# Sheet1.net
KiCad netlist of a schematic drawn in Altium Designer
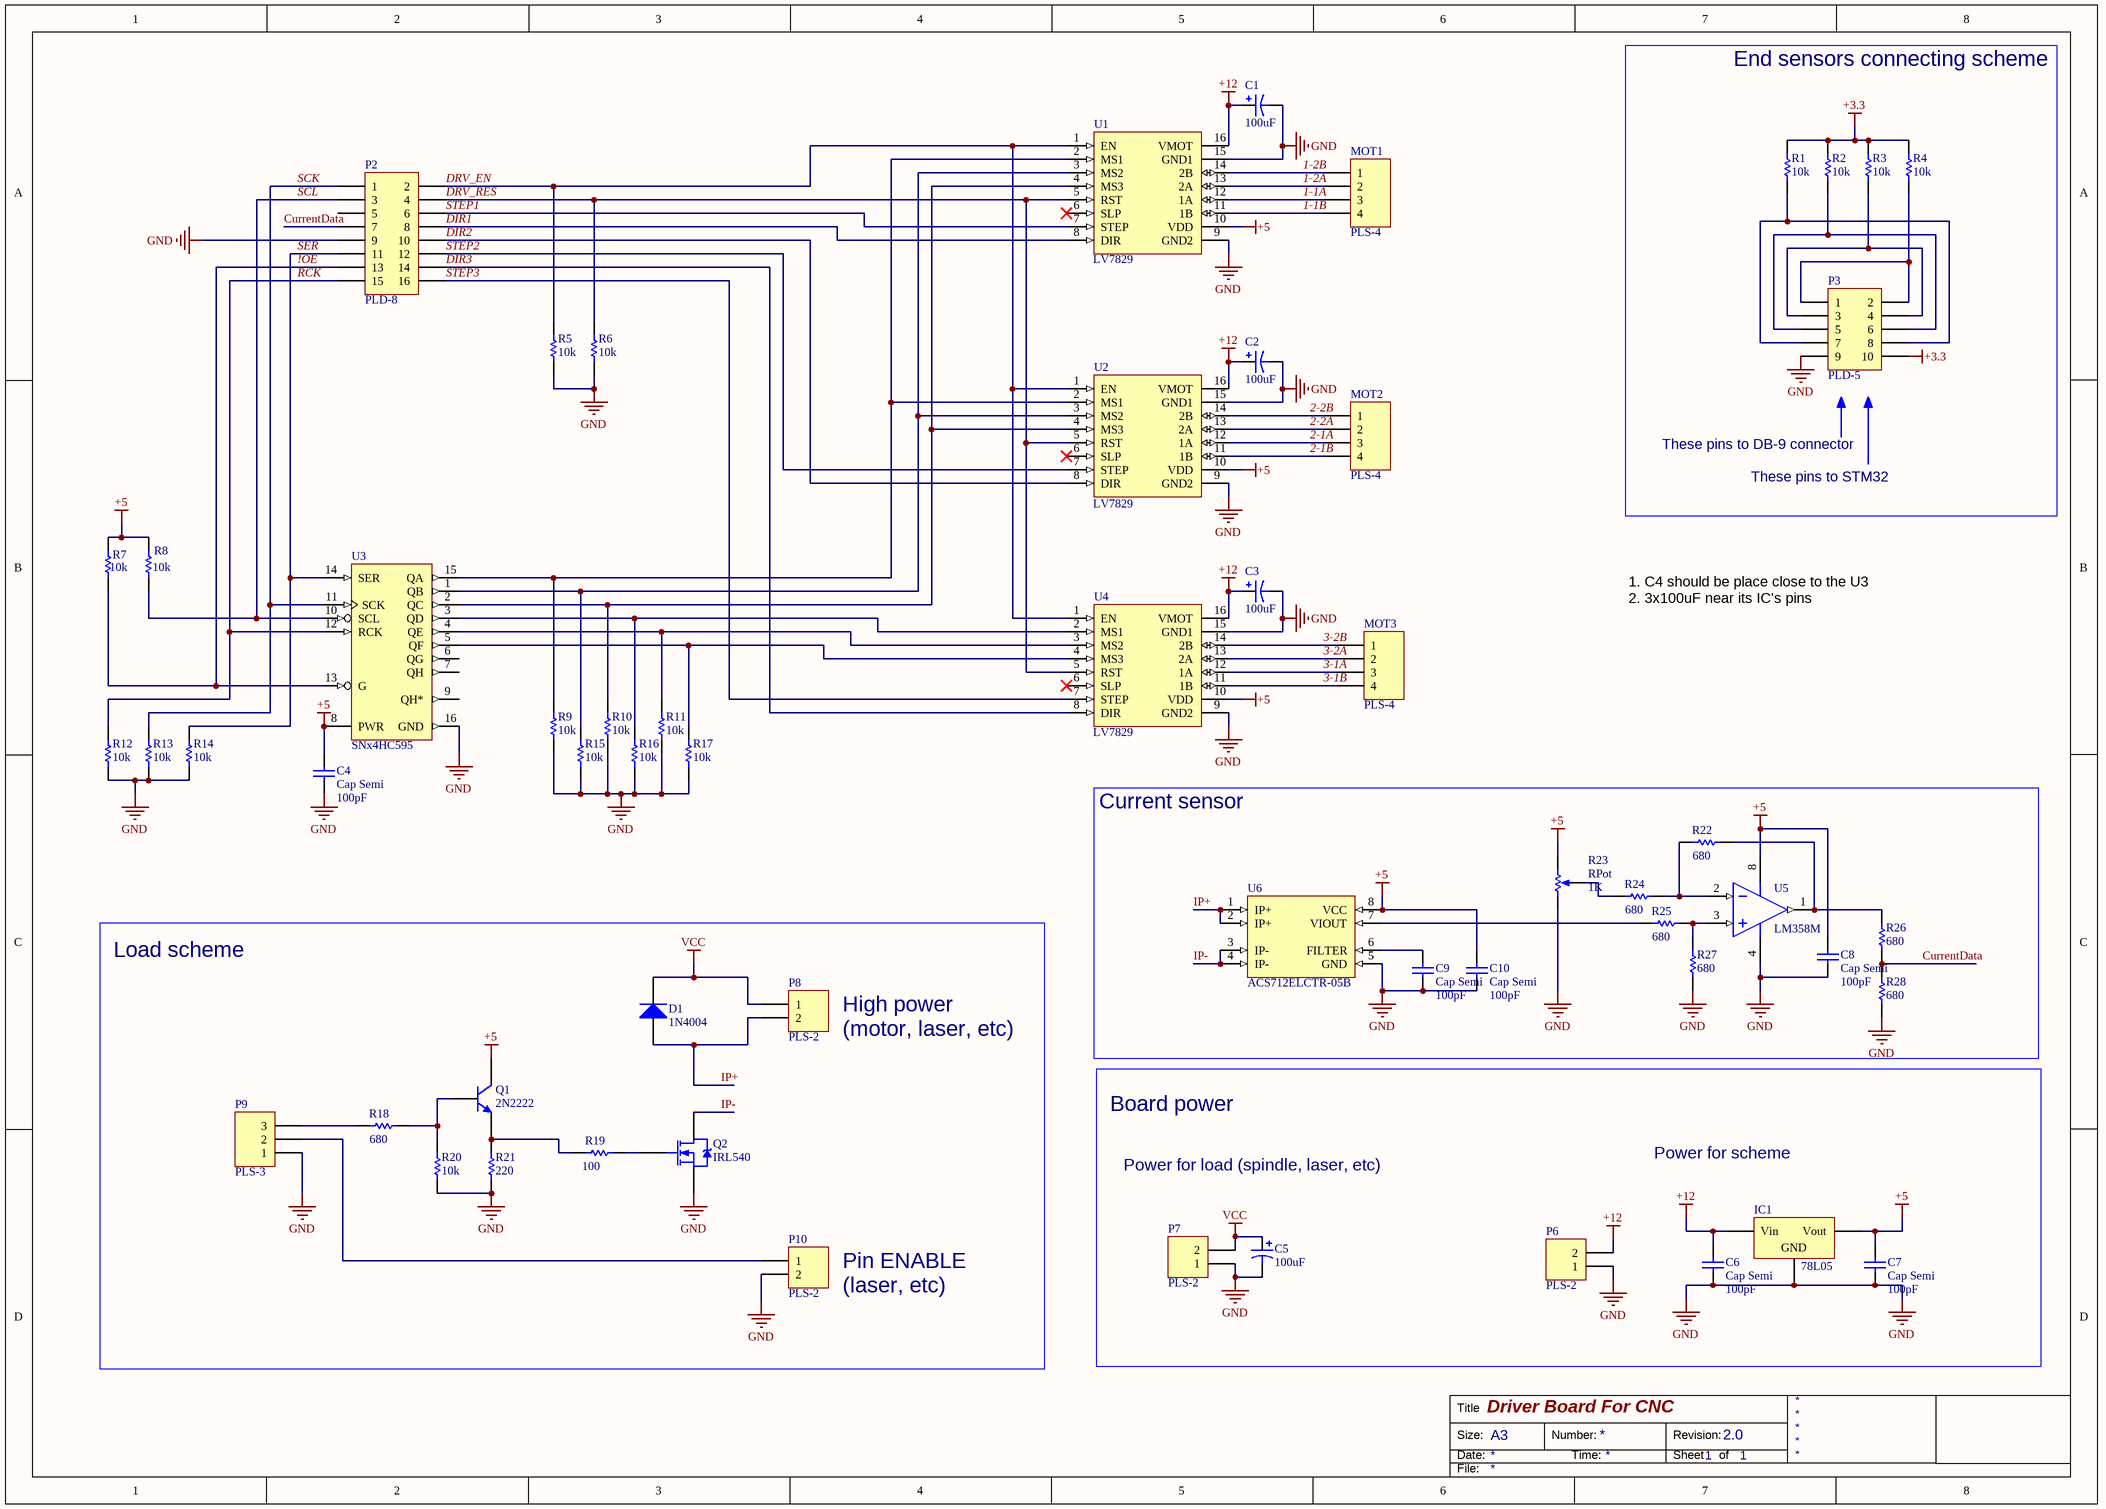
[diagram p0: Sheet1.SchDoc]

(export (version "E")
  (design (tool "Eeschema 10.0.6"))
  (components
    (comp (ref "C1")
      (value "100uF")
      (footprint "UD-6,3X5,8_NICHICON")
      (description "Polarized Capacitor (Radial)")
      (fields (field (name "Comment") "Cap Pol1") (field (name "PUBLISHER") "Altium Limited"))
      (libsource (lib "DriverBoardForCNC") (part "Cap Pol1"))
    )
    (comp (ref "C2")
      (value "100uF")
      (footprint "UD-6,3X5,8_NICHICON")
      (description "Polarized Capacitor (Radial)")
      (fields (field (name "Comment") "Cap Pol1") (field (name "PUBLISHER") "Altium Limited"))
      (libsource (lib "DriverBoardForCNC") (part "Cap Pol1"))
    )
    (comp (ref "C3")
      (value "100uF")
      (footprint "UD-6,3X5,8_NICHICON")
      (description "Polarized Capacitor (Radial)")
      (fields (field (name "Comment") "Cap Pol1") (field (name "PUBLISHER") "Altium Limited"))
      (libsource (lib "DriverBoardForCNC") (part "Cap Pol1"))
    )
    (comp (ref "C4")
      (value "Cap Semi")
      (footprint "C1206")
      (description "Capacitor (Semiconductor SIM Model)")
      (fields (field (name "ALTIUM_VALUE") "100pF") (field (name "PUBLISHER") "Altium Limited"))
      (libsource (lib "USB-RS485-unit") (part "Cap Semi"))
    )
    (comp (ref "C5")
      (value "100uF")
      (footprint "UD-6,3X5,8_NICHICON")
      (description "Polarized Capacitor (Radial)")
      (fields (field (name "Comment") "Cap Pol1") (field (name "PUBLISHER") "Altium Limited"))
      (libsource (lib "DriverBoardForCNC") (part "Cap Pol1"))
    )
    (comp (ref "C6")
      (value "Cap Semi")
      (footprint "C1206")
      (description "Capacitor (Semiconductor SIM Model)")
      (fields (field (name "ALTIUM_VALUE") "100pF") (field (name "PUBLISHER") "Altium Limited"))
      (libsource (lib "USB-RS485-unit") (part "Cap Semi"))
    )
    (comp (ref "C7")
      (value "Cap Semi")
      (footprint "C1206")
      (description "Capacitor (Semiconductor SIM Model)")
      (fields (field (name "ALTIUM_VALUE") "100pF") (field (name "PUBLISHER") "Altium Limited"))
      (libsource (lib "USB-RS485-unit") (part "Cap Semi"))
    )
    (comp (ref "C8")
      (value "Cap Semi")
      (footprint "C1206")
      (description "Capacitor (Semiconductor SIM Model)")
      (fields (field (name "ALTIUM_VALUE") "100pF") (field (name "PUBLISHER") "Altium Limited"))
      (libsource (lib "USB-RS485-unit") (part "Cap Semi"))
    )
    (comp (ref "C9")
      (value "Cap Semi")
      (footprint "C1206")
      (description "Capacitor (Semiconductor SIM Model)")
      (fields (field (name "ALTIUM_VALUE") "100pF") (field (name "PUBLISHER") "Altium Limited"))
      (libsource (lib "USB-RS485-unit") (part "Cap Semi"))
    )
    (comp (ref "C10")
      (value "Cap Semi")
      (footprint "C1206")
      (description "Capacitor (Semiconductor SIM Model)")
      (fields (field (name "ALTIUM_VALUE") "100pF") (field (name "PUBLISHER") "Altium Limited"))
      (libsource (lib "USB-RS485-unit") (part "Cap Semi"))
    )
    (comp (ref "D1")
      (value "1N4004")
      (footprint "DO-41")
      (description "1 Amp General Purpose Rectifier")
      (fields (field (name "PUBLISHER") "Altium Limited"))
      (libsource (lib "Miscellaneous Devices") (part "Diode 1N4004"))
    )
    (comp (ref "IC1")
      (value "78L05")
      (footprint "TO92")
      (description "Voltage Regulator")
      (fields (field (name "PUBLISHER") "Altium Limited"))
      (libsource (lib "DriverBoardForCNC") (part "Volt Reg"))
    )
    (comp (ref "MOT1")
      (value "PLS-4")
      (footprint "HDR1X4")
      (description "Header, 4-Pin")
      (fields (field (name "PUBLISHER") "Altium Limited"))
      (libsource (lib "Miscellaneous Connectors") (part "Header 4"))
    )
    (comp (ref "MOT2")
      (value "PLS-4")
      (footprint "HDR1X4")
      (description "Header, 4-Pin")
      (fields (field (name "PUBLISHER") "Altium Limited"))
      (libsource (lib "Miscellaneous Connectors") (part "Header 4"))
    )
    (comp (ref "MOT3")
      (value "PLS-4")
      (footprint "HDR1X4")
      (description "Header, 4-Pin")
      (fields (field (name "PUBLISHER") "Altium Limited"))
      (libsource (lib "Miscellaneous Connectors") (part "Header 4"))
    )
    (comp (ref "P2")
      (value "PLD-8")
      (footprint "HDR2X8")
      (description "Header, 8-Pin, Dual row")
      (fields (field (name "PUBLISHER") "Altium Limited"))
      (libsource (lib "Miscellaneous Connectors") (part "Header 8X2"))
    )
    (comp (ref "P3")
      (value "PLD-5")
      (footprint "HDR2X5")
      (description "Header, 5-Pin, Dual row")
      (fields (field (name "PUBLISHER") "Altium Limited"))
      (libsource (lib "Miscellaneous Connectors") (part "Header 5X2"))
    )
    (comp (ref "P6")
      (value "PLS-2")
      (footprint "W237-102")
      (description "Header, 2-Pin")
      (fields (field (name "MANUFACTURER") "AMPHENOL") (field (name "PUBLISHER") "Altium Limited"))
      (libsource (lib "USB-RS485-unit") (part "Header 2"))
    )
    (comp (ref "P7")
      (value "PLS-2")
      (footprint "W237-102")
      (description "Header, 2-Pin")
      (fields (field (name "MANUFACTURER") "AMPHENOL") (field (name "PUBLISHER") "Altium Limited"))
      (libsource (lib "USB-RS485-unit") (part "Header 2"))
    )
    (comp (ref "P8")
      (value "PLS-2")
      (footprint "W237-102")
      (description "Header, 2-Pin")
      (fields (field (name "MANUFACTURER") "AMPHENOL") (field (name "PUBLISHER") "Altium Limited"))
      (libsource (lib "") (part "Header 2_1"))
    )
    (comp (ref "P9")
      (value "PLS-3")
      (footprint "HDR1X3")
      (description "Header, 3-Pin")
      (fields (field (name "PUBLISHER") "Altium Limited"))
      (libsource (lib "Miscellaneous Connectors") (part "Header 3"))
    )
    (comp (ref "P10")
      (value "PLS-2")
      (footprint "HDR1X2")
      (description "Header, 2-Pin")
      (fields (field (name "MANUFACTURER") "AMPHENOL") (field (name "PUBLISHER") "Altium Limited"))
      (libsource (lib "") (part "Header 2_1"))
    )
    (comp (ref "Q1")
      (value "2N2222")
      (footprint "TO92")
      (description "NPN Bipolar Transistor")
      (fields (field (name "PUBLISHER") "Altium Limited"))
      (libsource (lib "Miscellaneous Devices") (part "NPN"))
    )
    (comp (ref "Q2")
      (value "IRL540")
      (footprint "TO220BV")
      (description "N-Channel Power MOSFET")
      (fields (field (name "PUBLISHER") "Altium Limited"))
      (libsource (lib "DriverBoardForCNC") (part "NMOS-2"))
    )
    (comp (ref "R1")
      (value "10k")
      (footprint "RES-0805")
      (fields (field (name "Comment") "ERA6Y") (field (name "PUBLISHER") "Altium Limited"))
      (libsource (lib "Panasonic Resistor") (part "ERA6Y"))
    )
    (comp (ref "R2")
      (value "10k")
      (footprint "RES-0805")
      (fields (field (name "Comment") "ERA6Y") (field (name "PUBLISHER") "Altium Limited"))
      (libsource (lib "Panasonic Resistor") (part "ERA6Y"))
    )
    (comp (ref "R3")
      (value "10k")
      (footprint "RES-0805")
      (fields (field (name "Comment") "ERA6Y") (field (name "PUBLISHER") "Altium Limited"))
      (libsource (lib "Panasonic Resistor") (part "ERA6Y"))
    )
    (comp (ref "R4")
      (value "10k")
      (footprint "RES-0805")
      (fields (field (name "Comment") "ERA6Y") (field (name "PUBLISHER") "Altium Limited"))
      (libsource (lib "Panasonic Resistor") (part "ERA6Y"))
    )
    (comp (ref "R5")
      (value "10k")
      (footprint "RES-0805")
      (fields (field (name "Comment") "ERA6Y") (field (name "PUBLISHER") "Altium Limited"))
      (libsource (lib "Panasonic Resistor") (part "ERA6Y"))
    )
    (comp (ref "R6")
      (value "10k")
      (footprint "RES-0805")
      (fields (field (name "Comment") "ERA6Y") (field (name "PUBLISHER") "Altium Limited"))
      (libsource (lib "Panasonic Resistor") (part "ERA6Y"))
    )
    (comp (ref "R7")
      (value "10k")
      (footprint "RES-0805")
      (fields (field (name "PUBLISHER") "Altium Limited"))
      (libsource (lib "Panasonic Resistor") (part "ERA6Y"))
    )
    (comp (ref "R8")
      (value "10k")
      (footprint "RES-0805")
      (fields (field (name "PUBLISHER") "Altium Limited"))
      (libsource (lib "Panasonic Resistor") (part "ERA6Y"))
    )
    (comp (ref "R9")
      (value "10k")
      (footprint "RES-0805")
      (fields (field (name "Comment") "ERA6Y") (field (name "PUBLISHER") "Altium Limited"))
      (libsource (lib "Panasonic Resistor") (part "ERA6Y"))
    )
    (comp (ref "R10")
      (value "10k")
      (footprint "RES-0805")
      (fields (field (name "Comment") "ERA6Y") (field (name "PUBLISHER") "Altium Limited"))
      (libsource (lib "Panasonic Resistor") (part "ERA6Y"))
    )
    (comp (ref "R11")
      (value "10k")
      (footprint "RES-0805")
      (fields (field (name "Comment") "ERA6Y") (field (name "PUBLISHER") "Altium Limited"))
      (libsource (lib "Panasonic Resistor") (part "ERA6Y"))
    )
    (comp (ref "R12")
      (value "10k")
      (footprint "RES-0805")
      (fields (field (name "Comment") "ERA6Y") (field (name "PUBLISHER") "Altium Limited"))
      (libsource (lib "Panasonic Resistor") (part "ERA6Y"))
    )
    (comp (ref "R13")
      (value "10k")
      (footprint "RES-0805")
      (fields (field (name "Comment") "ERA6Y") (field (name "PUBLISHER") "Altium Limited"))
      (libsource (lib "Panasonic Resistor") (part "ERA6Y"))
    )
    (comp (ref "R14")
      (value "10k")
      (footprint "RES-0805")
      (fields (field (name "Comment") "ERA6Y") (field (name "PUBLISHER") "Altium Limited"))
      (libsource (lib "Panasonic Resistor") (part "ERA6Y"))
    )
    (comp (ref "R15")
      (value "10k")
      (footprint "RES-0805")
      (fields (field (name "Comment") "ERA6Y") (field (name "PUBLISHER") "Altium Limited"))
      (libsource (lib "Panasonic Resistor") (part "ERA6Y"))
    )
    (comp (ref "R16")
      (value "10k")
      (footprint "RES-0805")
      (fields (field (name "Comment") "ERA6Y") (field (name "PUBLISHER") "Altium Limited"))
      (libsource (lib "Panasonic Resistor") (part "ERA6Y"))
    )
    (comp (ref "R17")
      (value "10k")
      (footprint "RES-0805")
      (fields (field (name "Comment") "ERA6Y") (field (name "PUBLISHER") "Altium Limited"))
      (libsource (lib "Panasonic Resistor") (part "ERA6Y"))
    )
    (comp (ref "R18")
      (value "680")
      (footprint "RES-0805")
      (fields (field (name "PUBLISHER") "Altium Limited"))
      (libsource (lib "Panasonic Resistor") (part "ERA6Y"))
    )
    (comp (ref "R19")
      (value "100")
      (footprint "RES-0805")
      (fields (field (name "Comment") "ERA6Y") (field (name "PUBLISHER") "Altium Limited"))
      (libsource (lib "Panasonic Resistor") (part "ERA6Y"))
    )
    (comp (ref "R20")
      (value "10k")
      (footprint "RES-0805")
      (fields (field (name "Comment") "ERA6Y") (field (name "PUBLISHER") "Altium Limited"))
      (libsource (lib "Panasonic Resistor") (part "ERA6Y"))
    )
    (comp (ref "R21")
      (value "220")
      (footprint "RES-0805")
      (fields (field (name "Comment") "ERA6Y") (field (name "PUBLISHER") "Altium Limited"))
      (libsource (lib "Panasonic Resistor") (part "ERA6Y"))
    )
    (comp (ref "R22")
      (value "680")
      (footprint "RES-0805")
      (fields (field (name "PUBLISHER") "Altium Limited"))
      (libsource (lib "Panasonic Resistor") (part "ERA6Y"))
    )
    (comp (ref "R23")
      (value "RPot")
      (footprint "VR5")
      (description "Potentiometer")
      (fields (field (name "ALTIUM_VALUE") "1K") (field (name "PUBLISHER") "Altium Limited"))
      (libsource (lib "DriverBoardForCNC") (part "RPot"))
    )
    (comp (ref "R24")
      (value "680")
      (footprint "RES-0805")
      (fields (field (name "PUBLISHER") "Altium Limited"))
      (libsource (lib "Panasonic Resistor") (part "ERA6Y"))
    )
    (comp (ref "R25")
      (value "680")
      (footprint "RES-1206")
      (fields (field (name "PUBLISHER") "Altium Limited"))
      (libsource (lib "Panasonic Resistor") (part "ERA6Y"))
    )
    (comp (ref "R26")
      (value "680")
      (footprint "RES-0805")
      (fields (field (name "PUBLISHER") "Altium Limited"))
      (libsource (lib "Panasonic Resistor") (part "ERA6Y"))
    )
    (comp (ref "R27")
      (value "680")
      (footprint "RES-0805")
      (fields (field (name "PUBLISHER") "Altium Limited"))
      (libsource (lib "Panasonic Resistor") (part "ERA6Y"))
    )
    (comp (ref "R28")
      (value "680")
      (footprint "RES-0805")
      (fields (field (name "PUBLISHER") "Altium Limited"))
      (libsource (lib "Panasonic Resistor") (part "ERA6Y"))
    )
    (comp (ref "U1")
      (value "LV7829")
      (footprint "LV8729_BREAKOUT")
      (description "Quad Bidir ESD protection")
      (fields
        (field (name "INTERNAL_PART_NUMBER") "MCD-00247")
        (field (name "MANUFACTURER_PART_NUMBER") "ESDA6V1BC6")
        (field (name "PROVIDED_BY") "SUBCO with ST control")
      )
      (libsource (lib "DriverBoardForCNC") (part "LV7829"))
    )
    (comp (ref "U2")
      (value "LV7829")
      (footprint "LV8729_BREAKOUT")
      (description "Quad Bidir ESD protection")
      (fields
        (field (name "INTERNAL_PART_NUMBER") "MCD-00247")
        (field (name "MANUFACTURER_PART_NUMBER") "ESDA6V1BC6")
        (field (name "PROVIDED_BY") "SUBCO with ST control")
      )
      (libsource (lib "DriverBoardForCNC") (part "LV7829"))
    )
    (comp (ref "U3")
      (value "SNx4HC595")
      (footprint "SO16")
      (description "Quad Bidir ESD protection")
      (fields
        (field (name "INTERNAL_PART_NUMBER") "MCD-00247")
        (field (name "MANUFACTURER_PART_NUMBER") "ESDA6V1BC6")
        (field (name "PROVIDED_BY") "SUBCO with ST control")
      )
      (libsource (lib "DriverBoardForCNC") (part "SNx4HC595"))
    )
    (comp (ref "U4")
      (value "LV7829")
      (footprint "LV8729_BREAKOUT")
      (description "Quad Bidir ESD protection")
      (fields
        (field (name "INTERNAL_PART_NUMBER") "MCD-00247")
        (field (name "MANUFACTURER_PART_NUMBER") "ESDA6V1BC6")
        (field (name "PROVIDED_BY") "SUBCO with ST control")
      )
      (libsource (lib "DriverBoardForCNC") (part "LV7829"))
    )
    (comp (ref "U5")
      (value "LM358M")
      (footprint "SO-8_L")
      (description "FET Operational Amplifier")
      (fields (field (name "PUBLISHER") "Altium Limited"))
      (libsource (lib "DriverBoardForCNC") (part "Op Amp"))
    )
    (comp (ref "U6")
      (value "ACS712ELCTR-05B")
      (footprint "SO-8_L")
      (description "Quad Bidir ESD protection")
      (fields
        (field (name "INTERNAL_PART_NUMBER") "MCD-00247")
        (field (name "MANUFACTURER_PART_NUMBER") "ESDA6V1BC6")
        (field (name "PROVIDED_BY") "SUBCO with ST control")
      )
      (libsource (lib "DriverBoardForCNC") (part "ACS712ELCTR-05B"))
    )
  )
  (nets
    (net (code "1") (name "+3.3") (class "Default")
      (node (ref "P3") (pin "10") (pinfunction "10_10") (pintype "passive"))
      (node (ref "R1") (pin "1") (pinfunction "1_1") (pintype "passive"))
      (node (ref "R2") (pin "1") (pinfunction "1_1") (pintype "passive"))
      (node (ref "R3") (pin "1") (pinfunction "1_1") (pintype "passive"))
      (node (ref "R4") (pin "1") (pinfunction "1_1") (pintype "passive"))
    )
    (net (code "2") (name "+5") (class "Default")
      (node (ref "C10") (pin "2") (pinfunction "2_2") (pintype "passive"))
      (node (ref "C4") (pin "2") (pinfunction "2_2") (pintype "passive"))
      (node (ref "C7") (pin "2") (pinfunction "2_2") (pintype "passive"))
      (node (ref "C8") (pin "1") (pinfunction "1_1") (pintype "passive"))
      (node (ref "IC1") (pin "3") (pinfunction "Vout_3") (pintype "passive"))
      (node (ref "Q1") (pin "1") (pinfunction "C_1") (pintype "passive"))
      (node (ref "R23") (pin "3") (pinfunction "BOT_3") (pintype "passive"))
      (node (ref "R7") (pin "1") (pinfunction "1_1") (pintype "passive"))
      (node (ref "R8") (pin "1") (pinfunction "1_1") (pintype "passive"))
      (node (ref "U1") (pin "10") (pinfunction "VDD_10") (pintype "power_in"))
      (node (ref "U2") (pin "10") (pinfunction "VDD_10") (pintype "power_in"))
      (node (ref "U3") (pin "8") (pinfunction "PWR_8") (pintype "power_in"))
      (node (ref "U4") (pin "10") (pinfunction "VDD_10") (pintype "power_in"))
      (node (ref "U5") (pin "8") (pinfunction "V+_8") (pintype "power_in"))
      (node (ref "U6") (pin "8") (pinfunction "VCC_8") (pintype "input"))
    )
    (net (code "3") (name "+12") (class "Default")
      (node (ref "C1") (pin "1") (pinfunction "1_1") (pintype "passive"))
      (node (ref "C2") (pin "1") (pinfunction "1_1") (pintype "passive"))
      (node (ref "C3") (pin "1") (pinfunction "1_1") (pintype "passive"))
      (node (ref "C6") (pin "2") (pinfunction "2_2") (pintype "passive"))
      (node (ref "IC1") (pin "1") (pinfunction "Vin_1") (pintype "passive"))
      (node (ref "P6") (pin "2") (pinfunction "2_2") (pintype "passive"))
      (node (ref "U1") (pin "16") (pinfunction "VMOT_16") (pintype "power_in"))
      (node (ref "U2") (pin "16") (pinfunction "VMOT_16") (pintype "power_in"))
      (node (ref "U4") (pin "16") (pinfunction "VMOT_16") (pintype "power_in"))
    )
    (net (code "4") (name "/!OE") (class "Default")
      (node (ref "P2") (pin "13") (pinfunction "13_13") (pintype "passive"))
      (node (ref "R7") (pin "2") (pinfunction "2_2") (pintype "passive"))
      (node (ref "U3") (pin "13") (pinfunction "G_13") (pintype "input"))
    )
    (net (code "5") (name "/1-1A") (class "Default")
      (node (ref "MOT1") (pin "3") (pinfunction "3_3") (pintype "passive"))
      (node (ref "U1") (pin "12") (pinfunction "1A_12") (pintype "bidirectional"))
    )
    (net (code "6") (name "/1-1B") (class "Default")
      (node (ref "MOT1") (pin "4") (pinfunction "4_4") (pintype "passive"))
      (node (ref "U1") (pin "11") (pinfunction "1B_11") (pintype "bidirectional"))
    )
    (net (code "7") (name "/1-2A") (class "Default")
      (node (ref "MOT1") (pin "2") (pinfunction "2_2") (pintype "passive"))
      (node (ref "U1") (pin "13") (pinfunction "2A_13") (pintype "bidirectional"))
    )
    (net (code "8") (name "/1-2B") (class "Default")
      (node (ref "MOT1") (pin "1") (pinfunction "1_1") (pintype "passive"))
      (node (ref "U1") (pin "14") (pinfunction "2B_14") (pintype "bidirectional"))
    )
    (net (code "9") (name "/2-1A") (class "Default")
      (node (ref "MOT2") (pin "3") (pinfunction "3_3") (pintype "passive"))
      (node (ref "U2") (pin "12") (pinfunction "1A_12") (pintype "bidirectional"))
    )
    (net (code "10") (name "/2-1B") (class "Default")
      (node (ref "MOT2") (pin "4") (pinfunction "4_4") (pintype "passive"))
      (node (ref "U2") (pin "11") (pinfunction "1B_11") (pintype "bidirectional"))
    )
    (net (code "11") (name "/2-2A") (class "Default")
      (node (ref "MOT2") (pin "2") (pinfunction "2_2") (pintype "passive"))
      (node (ref "U2") (pin "13") (pinfunction "2A_13") (pintype "bidirectional"))
    )
    (net (code "12") (name "/2-2B") (class "Default")
      (node (ref "MOT2") (pin "1") (pinfunction "1_1") (pintype "passive"))
      (node (ref "U2") (pin "14") (pinfunction "2B_14") (pintype "bidirectional"))
    )
    (net (code "13") (name "/3-1A") (class "Default")
      (node (ref "MOT3") (pin "3") (pinfunction "3_3") (pintype "passive"))
      (node (ref "U4") (pin "12") (pinfunction "1A_12") (pintype "bidirectional"))
    )
    (net (code "14") (name "/3-1B") (class "Default")
      (node (ref "MOT3") (pin "4") (pinfunction "4_4") (pintype "passive"))
      (node (ref "U4") (pin "11") (pinfunction "1B_11") (pintype "bidirectional"))
    )
    (net (code "15") (name "/3-2A") (class "Default")
      (node (ref "MOT3") (pin "2") (pinfunction "2_2") (pintype "passive"))
      (node (ref "U4") (pin "13") (pinfunction "2A_13") (pintype "bidirectional"))
    )
    (net (code "16") (name "/3-2B") (class "Default")
      (node (ref "MOT3") (pin "1") (pinfunction "1_1") (pintype "passive"))
      (node (ref "U4") (pin "14") (pinfunction "2B_14") (pintype "bidirectional"))
    )
    (net (code "17") (name "/CurrentData") (class "Default")
      (node (ref "P2") (pin "7") (pinfunction "7_7") (pintype "passive"))
      (node (ref "R26") (pin "2") (pinfunction "2_2") (pintype "passive"))
      (node (ref "R28") (pin "1") (pinfunction "1_1") (pintype "passive"))
    )
    (net (code "18") (name "/DIR1") (class "Default")
      (node (ref "P2") (pin "8") (pinfunction "8_8") (pintype "passive"))
      (node (ref "U1") (pin "8") (pinfunction "DIR_8") (pintype "input"))
    )
    (net (code "19") (name "/DIR2") (class "Default")
      (node (ref "P2") (pin "10") (pinfunction "10_10") (pintype "passive"))
      (node (ref "U2") (pin "8") (pinfunction "DIR_8") (pintype "input"))
    )
    (net (code "20") (name "/DIR3") (class "Default")
      (node (ref "P2") (pin "14") (pinfunction "14_14") (pintype "passive"))
      (node (ref "U4") (pin "8") (pinfunction "DIR_8") (pintype "input"))
    )
    (net (code "21") (name "/DRV_EN") (class "Default")
      (node (ref "P2") (pin "2") (pinfunction "2_2") (pintype "passive"))
      (node (ref "R5") (pin "1") (pinfunction "1_1") (pintype "passive"))
      (node (ref "U1") (pin "1") (pinfunction "EN_1") (pintype "input"))
      (node (ref "U2") (pin "1") (pinfunction "EN_1") (pintype "input"))
      (node (ref "U4") (pin "1") (pinfunction "EN_1") (pintype "input"))
    )
    (net (code "22") (name "/DRV_RES") (class "Default")
      (node (ref "P2") (pin "4") (pinfunction "4_4") (pintype "passive"))
      (node (ref "R6") (pin "1") (pinfunction "1_1") (pintype "passive"))
      (node (ref "U1") (pin "5") (pinfunction "RST_5") (pintype "input"))
      (node (ref "U2") (pin "5") (pinfunction "RST_5") (pintype "input"))
      (node (ref "U4") (pin "5") (pinfunction "RST_5") (pintype "input"))
    )
    (net (code "23") (name "/IP+") (class "Default")
      (node (ref "D1") (pin "1") (pinfunction "A_1") (pintype "passive"))
      (node (ref "P8") (pin "2") (pinfunction "2_2") (pintype "passive"))
      (node (ref "U6") (pin "1") (pinfunction "IP+_1") (pintype "input"))
      (node (ref "U6") (pin "2") (pinfunction "IP+_2") (pintype "input"))
    )
    (net (code "24") (name "/IP-") (class "Default")
      (node (ref "Q2") (pin "2") (pinfunction "D_2") (pintype "passive"))
      (node (ref "U6") (pin "3") (pinfunction "IP-_3") (pintype "input"))
      (node (ref "U6") (pin "4") (pinfunction "IP-_4") (pintype "input"))
    )
    (net (code "25") (name "/RCK") (class "Default")
      (node (ref "P2") (pin "15") (pinfunction "15_15") (pintype "passive"))
      (node (ref "R12") (pin "1") (pinfunction "1_1") (pintype "passive"))
      (node (ref "U3") (pin "12") (pinfunction "RCK_12") (pintype "input"))
    )
    (net (code "26") (name "/SCK") (class "Default")
      (node (ref "P2") (pin "1") (pinfunction "1_1") (pintype "passive"))
      (node (ref "R13") (pin "1") (pinfunction "1_1") (pintype "passive"))
      (node (ref "U3") (pin "11") (pinfunction "SCK_11") (pintype "input"))
    )
    (net (code "27") (name "/SCL") (class "Default")
      (node (ref "P2") (pin "3") (pinfunction "3_3") (pintype "passive"))
      (node (ref "R8") (pin "2") (pinfunction "2_2") (pintype "passive"))
      (node (ref "U3") (pin "10") (pinfunction "SCL_10") (pintype "input"))
    )
    (net (code "28") (name "/SER") (class "Default")
      (node (ref "P2") (pin "11") (pinfunction "11_11") (pintype "passive"))
      (node (ref "R14") (pin "1") (pinfunction "1_1") (pintype "passive"))
      (node (ref "U3") (pin "14") (pinfunction "SER_14") (pintype "input"))
    )
    (net (code "29") (name "/STEP1") (class "Default")
      (node (ref "P2") (pin "6") (pinfunction "6_6") (pintype "passive"))
      (node (ref "U1") (pin "7") (pinfunction "STEP_7") (pintype "input"))
    )
    (net (code "30") (name "/STEP2") (class "Default")
      (node (ref "P2") (pin "12") (pinfunction "12_12") (pintype "passive"))
      (node (ref "U2") (pin "7") (pinfunction "STEP_7") (pintype "input"))
    )
    (net (code "31") (name "/STEP3") (class "Default")
      (node (ref "P2") (pin "16") (pinfunction "16_16") (pintype "passive"))
      (node (ref "U4") (pin "7") (pinfunction "STEP_7") (pintype "input"))
    )
    (net (code "32") (name "GND") (class "Default")
      (node (ref "C1") (pin "2") (pinfunction "2_2") (pintype "passive"))
      (node (ref "C10") (pin "1") (pinfunction "1_1") (pintype "passive"))
      (node (ref "C2") (pin "2") (pinfunction "2_2") (pintype "passive"))
      (node (ref "C3") (pin "2") (pinfunction "2_2") (pintype "passive"))
      (node (ref "C4") (pin "1") (pinfunction "1_1") (pintype "passive"))
      (node (ref "C5") (pin "2") (pinfunction "2_2") (pintype "passive"))
      (node (ref "C6") (pin "1") (pinfunction "1_1") (pintype "passive"))
      (node (ref "C7") (pin "1") (pinfunction "1_1") (pintype "passive"))
      (node (ref "C8") (pin "2") (pinfunction "2_2") (pintype "passive"))
      (node (ref "C9") (pin "1") (pinfunction "1_1") (pintype "passive"))
      (node (ref "IC1") (pin "2") (pinfunction "GND_2") (pintype "passive"))
      (node (ref "P10") (pin "2") (pinfunction "2_2") (pintype "passive"))
      (node (ref "P2") (pin "9") (pinfunction "9_9") (pintype "passive"))
      (node (ref "P3") (pin "9") (pinfunction "9_9") (pintype "passive"))
      (node (ref "P6") (pin "1") (pinfunction "1_1") (pintype "passive"))
      (node (ref "P7") (pin "1") (pinfunction "1_1") (pintype "passive"))
      (node (ref "P9") (pin "1") (pinfunction "1_1") (pintype "passive"))
      (node (ref "Q2") (pin "3") (pinfunction "S_3") (pintype "passive"))
      (node (ref "R10") (pin "2") (pinfunction "2_2") (pintype "passive"))
      (node (ref "R11") (pin "2") (pinfunction "2_2") (pintype "passive"))
      (node (ref "R12") (pin "2") (pinfunction "2_2") (pintype "passive"))
      (node (ref "R13") (pin "2") (pinfunction "2_2") (pintype "passive"))
      (node (ref "R14") (pin "2") (pinfunction "2_2") (pintype "passive"))
      (node (ref "R15") (pin "2") (pinfunction "2_2") (pintype "passive"))
      (node (ref "R16") (pin "2") (pinfunction "2_2") (pintype "passive"))
      (node (ref "R17") (pin "2") (pinfunction "2_2") (pintype "passive"))
      (node (ref "R20") (pin "2") (pinfunction "2_2") (pintype "passive"))
      (node (ref "R21") (pin "2") (pinfunction "2_2") (pintype "passive"))
      (node (ref "R23") (pin "1") (pinfunction "TOP_1") (pintype "passive"))
      (node (ref "R27") (pin "2") (pinfunction "2_2") (pintype "passive"))
      (node (ref "R28") (pin "2") (pinfunction "2_2") (pintype "passive"))
      (node (ref "R5") (pin "2") (pinfunction "2_2") (pintype "passive"))
      (node (ref "R6") (pin "2") (pinfunction "2_2") (pintype "passive"))
      (node (ref "R9") (pin "2") (pinfunction "2_2") (pintype "passive"))
      (node (ref "U1") (pin "15") (pinfunction "GND1_15") (pintype "power_in"))
      (node (ref "U1") (pin "9") (pinfunction "GND2_9") (pintype "power_in"))
      (node (ref "U2") (pin "15") (pinfunction "GND1_15") (pintype "power_in"))
      (node (ref "U2") (pin "9") (pinfunction "GND2_9") (pintype "power_in"))
      (node (ref "U3") (pin "16") (pinfunction "GND_16") (pintype "output"))
      (node (ref "U4") (pin "15") (pinfunction "GND1_15") (pintype "power_in"))
      (node (ref "U4") (pin "9") (pinfunction "GND2_9") (pintype "power_in"))
      (node (ref "U5") (pin "4") (pinfunction "V-_4") (pintype "power_in"))
      (node (ref "U6") (pin "5") (pinfunction "GND_5") (pintype "input"))
    )
    (net (code "33") (name "Net-(P3-Pad1)") (class "Default")
      (node (ref "P3") (pin "1") (pinfunction "1_1") (pintype "passive"))
      (node (ref "P3") (pin "2") (pinfunction "2_2") (pintype "passive"))
      (node (ref "R4") (pin "2") (pinfunction "2_2") (pintype "passive"))
    )
    (net (code "34") (name "Net-(P3-Pad3)") (class "Default")
      (node (ref "P3") (pin "3") (pinfunction "3_3") (pintype "passive"))
      (node (ref "P3") (pin "4") (pinfunction "4_4") (pintype "passive"))
      (node (ref "R3") (pin "2") (pinfunction "2_2") (pintype "passive"))
    )
    (net (code "35") (name "Net-(P3-Pad5)") (class "Default")
      (node (ref "P3") (pin "5") (pinfunction "5_5") (pintype "passive"))
      (node (ref "P3") (pin "6") (pinfunction "6_6") (pintype "passive"))
      (node (ref "R2") (pin "2") (pinfunction "2_2") (pintype "passive"))
    )
    (net (code "36") (name "Net-(P3-Pad7)") (class "Default")
      (node (ref "P3") (pin "7") (pinfunction "7_7") (pintype "passive"))
      (node (ref "P3") (pin "8") (pinfunction "8_8") (pintype "passive"))
      (node (ref "R1") (pin "2") (pinfunction "2_2") (pintype "passive"))
    )
    (net (code "37") (name "Net-(P9-Pad3)") (class "Default")
      (node (ref "P9") (pin "3") (pinfunction "3_3") (pintype "passive"))
      (node (ref "R18") (pin "2") (pinfunction "2_2") (pintype "passive"))
    )
    (net (code "38") (name "Net-(P10-Pad1)") (class "Default")
      (node (ref "P10") (pin "1") (pinfunction "1_1") (pintype "passive"))
      (node (ref "P9") (pin "2") (pinfunction "2_2") (pintype "passive"))
    )
    (net (code "39") (name "Net-(Q1-B)") (class "Default")
      (node (ref "Q1") (pin "2") (pinfunction "B_2") (pintype "passive"))
      (node (ref "R18") (pin "1") (pinfunction "1_1") (pintype "passive"))
      (node (ref "R20") (pin "1") (pinfunction "1_1") (pintype "passive"))
    )
    (net (code "40") (name "Net-(Q1-E)") (class "Default")
      (node (ref "Q1") (pin "3") (pinfunction "E_3") (pintype "passive"))
      (node (ref "R19") (pin "2") (pinfunction "2_2") (pintype "passive"))
      (node (ref "R21") (pin "1") (pinfunction "1_1") (pintype "passive"))
    )
    (net (code "41") (name "Net-(Q2-G)") (class "Default")
      (node (ref "Q2") (pin "1") (pinfunction "G_1") (pintype "passive"))
      (node (ref "R19") (pin "1") (pinfunction "1_1") (pintype "passive"))
    )
    (net (code "42") (name "Net-(R23-TAP)") (class "Default")
      (node (ref "R23") (pin "2") (pinfunction "TAP_2") (pintype "passive"))
      (node (ref "R24") (pin "2") (pinfunction "2_2") (pintype "passive"))
    )
    (net (code "43") (name "Net-(U1-MS1)") (class "Default")
      (node (ref "R9") (pin "1") (pinfunction "1_1") (pintype "passive"))
      (node (ref "U1") (pin "2") (pinfunction "MS1_2") (pintype "input"))
      (node (ref "U2") (pin "2") (pinfunction "MS1_2") (pintype "input"))
      (node (ref "U3") (pin "15") (pinfunction "QA_15") (pintype "output"))
    )
    (net (code "44") (name "Net-(U1-MS2)") (class "Default")
      (node (ref "R15") (pin "1") (pinfunction "1_1") (pintype "passive"))
      (node (ref "U1") (pin "3") (pinfunction "MS2_3") (pintype "input"))
      (node (ref "U2") (pin "3") (pinfunction "MS2_3") (pintype "input"))
      (node (ref "U3") (pin "1") (pinfunction "QB_1") (pintype "output"))
    )
    (net (code "45") (name "Net-(U1-MS3)") (class "Default")
      (node (ref "R10") (pin "1") (pinfunction "1_1") (pintype "passive"))
      (node (ref "U1") (pin "4") (pinfunction "MS3_4") (pintype "input"))
      (node (ref "U2") (pin "4") (pinfunction "MS3_4") (pintype "input"))
      (node (ref "U3") (pin "2") (pinfunction "QC_2") (pintype "output"))
    )
    (net (code "46") (name "Net-(U3-QD)") (class "Default")
      (node (ref "R16") (pin "1") (pinfunction "1_1") (pintype "passive"))
      (node (ref "U3") (pin "3") (pinfunction "QD_3") (pintype "output"))
      (node (ref "U4") (pin "2") (pinfunction "MS1_2") (pintype "input"))
    )
    (net (code "47") (name "Net-(U3-QE)") (class "Default")
      (node (ref "R11") (pin "1") (pinfunction "1_1") (pintype "passive"))
      (node (ref "U3") (pin "4") (pinfunction "QE_4") (pintype "output"))
      (node (ref "U4") (pin "3") (pinfunction "MS2_3") (pintype "input"))
    )
    (net (code "48") (name "Net-(U3-QF)") (class "Default")
      (node (ref "R17") (pin "1") (pinfunction "1_1") (pintype "passive"))
      (node (ref "U3") (pin "5") (pinfunction "QF_5") (pintype "output"))
      (node (ref "U4") (pin "4") (pinfunction "MS3_4") (pintype "input"))
    )
    (net (code "49") (name "Net-(U5-IN+)") (class "Default")
      (node (ref "R25") (pin "1") (pinfunction "1_1") (pintype "passive"))
      (node (ref "R27") (pin "1") (pinfunction "1_1") (pintype "passive"))
      (node (ref "U5") (pin "3") (pinfunction "IN+_3") (pintype "input"))
    )
    (net (code "50") (name "Net-(U5-IN-)") (class "Default")
      (node (ref "R22") (pin "2") (pinfunction "2_2") (pintype "passive"))
      (node (ref "R24") (pin "1") (pinfunction "1_1") (pintype "passive"))
      (node (ref "U5") (pin "2") (pinfunction "IN-_2") (pintype "input"))
    )
    (net (code "51") (name "Net-(U5-OUT)") (class "Default")
      (node (ref "R22") (pin "1") (pinfunction "1_1") (pintype "passive"))
      (node (ref "R26") (pin "1") (pinfunction "1_1") (pintype "passive"))
      (node (ref "U5") (pin "1") (pinfunction "OUT_1") (pintype "output"))
    )
    (net (code "52") (name "Net-(U6-FILTER)") (class "Default")
      (node (ref "C9") (pin "2") (pinfunction "2_2") (pintype "passive"))
      (node (ref "U6") (pin "6") (pinfunction "FILTER_6") (pintype "input"))
    )
    (net (code "53") (name "Net-(U6-VIOUT)") (class "Default")
      (node (ref "R25") (pin "2") (pinfunction "2_2") (pintype "passive"))
      (node (ref "U6") (pin "7") (pinfunction "VIOUT_7") (pintype "input"))
    )
    (net (code "54") (name "VCC") (class "Default")
      (node (ref "C5") (pin "1") (pinfunction "1_1") (pintype "passive"))
      (node (ref "D1") (pin "2") (pinfunction "K_2") (pintype "passive"))
      (node (ref "P7") (pin "2") (pinfunction "2_2") (pintype "passive"))
      (node (ref "P8") (pin "1") (pinfunction "1_1") (pintype "passive"))
    )
    (net (code "55") (name "unconnected-(P2-Pad5)") (class "Default")
      (node (ref "P2") (pin "5") (pinfunction "5_5") (pintype "passive"))
    )
    (net (code "56") (name "unconnected-(U1-SLP-Pad6)") (class "Default")
      (node (ref "U1") (pin "6") (pinfunction "SLP_6") (pintype "input+no_connect"))
    )
    (net (code "57") (name "unconnected-(U2-SLP-Pad6)") (class "Default")
      (node (ref "U2") (pin "6") (pinfunction "SLP_6") (pintype "input+no_connect"))
    )
    (net (code "58") (name "unconnected-(U3-QG-Pad6)") (class "Default")
      (node (ref "U3") (pin "6") (pinfunction "QG_6") (pintype "output"))
    )
    (net (code "59") (name "unconnected-(U3-QH*-Pad9)") (class "Default")
      (node (ref "U3") (pin "9") (pinfunction "QH*_9") (pintype "output"))
    )
    (net (code "60") (name "unconnected-(U3-QH-Pad7)") (class "Default")
      (node (ref "U3") (pin "7") (pinfunction "QH_7") (pintype "output"))
    )
    (net (code "61") (name "unconnected-(U4-SLP-Pad6)") (class "Default")
      (node (ref "U4") (pin "6") (pinfunction "SLP_6") (pintype "input+no_connect"))
    )
  )
)
